# Helmet_Drop_V1_5.net
KiCad netlist of a schematic drawn in EAGLE
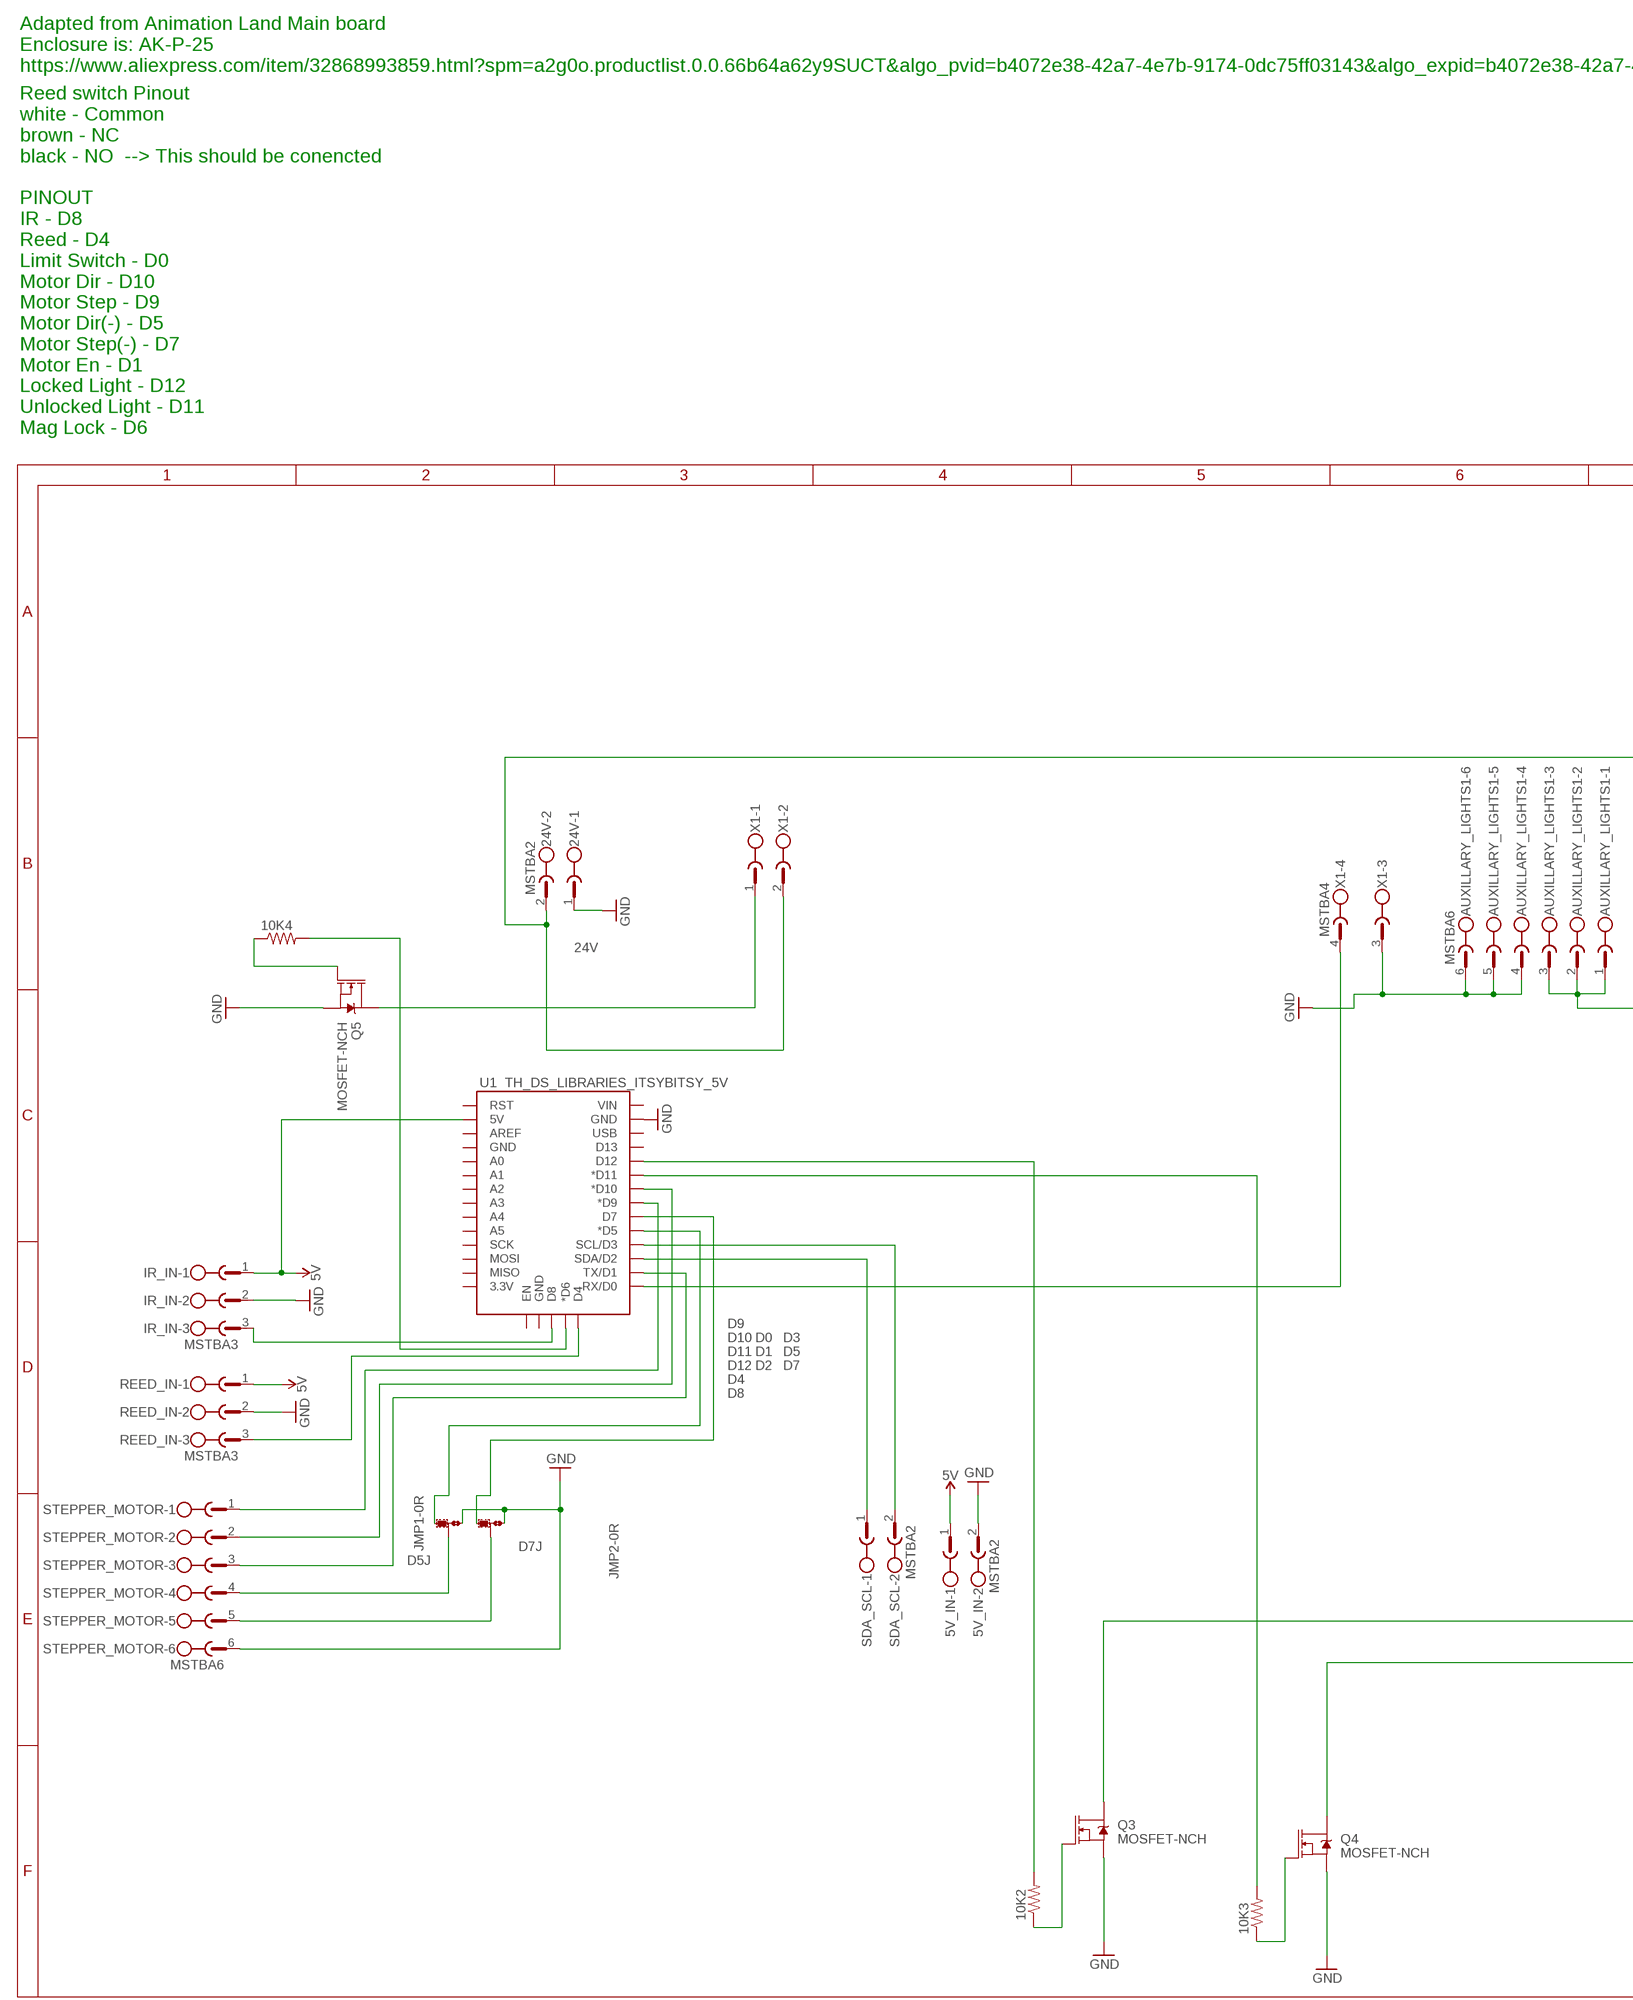
[diagram p0: schematic, sheet 1, part 1 of 2]
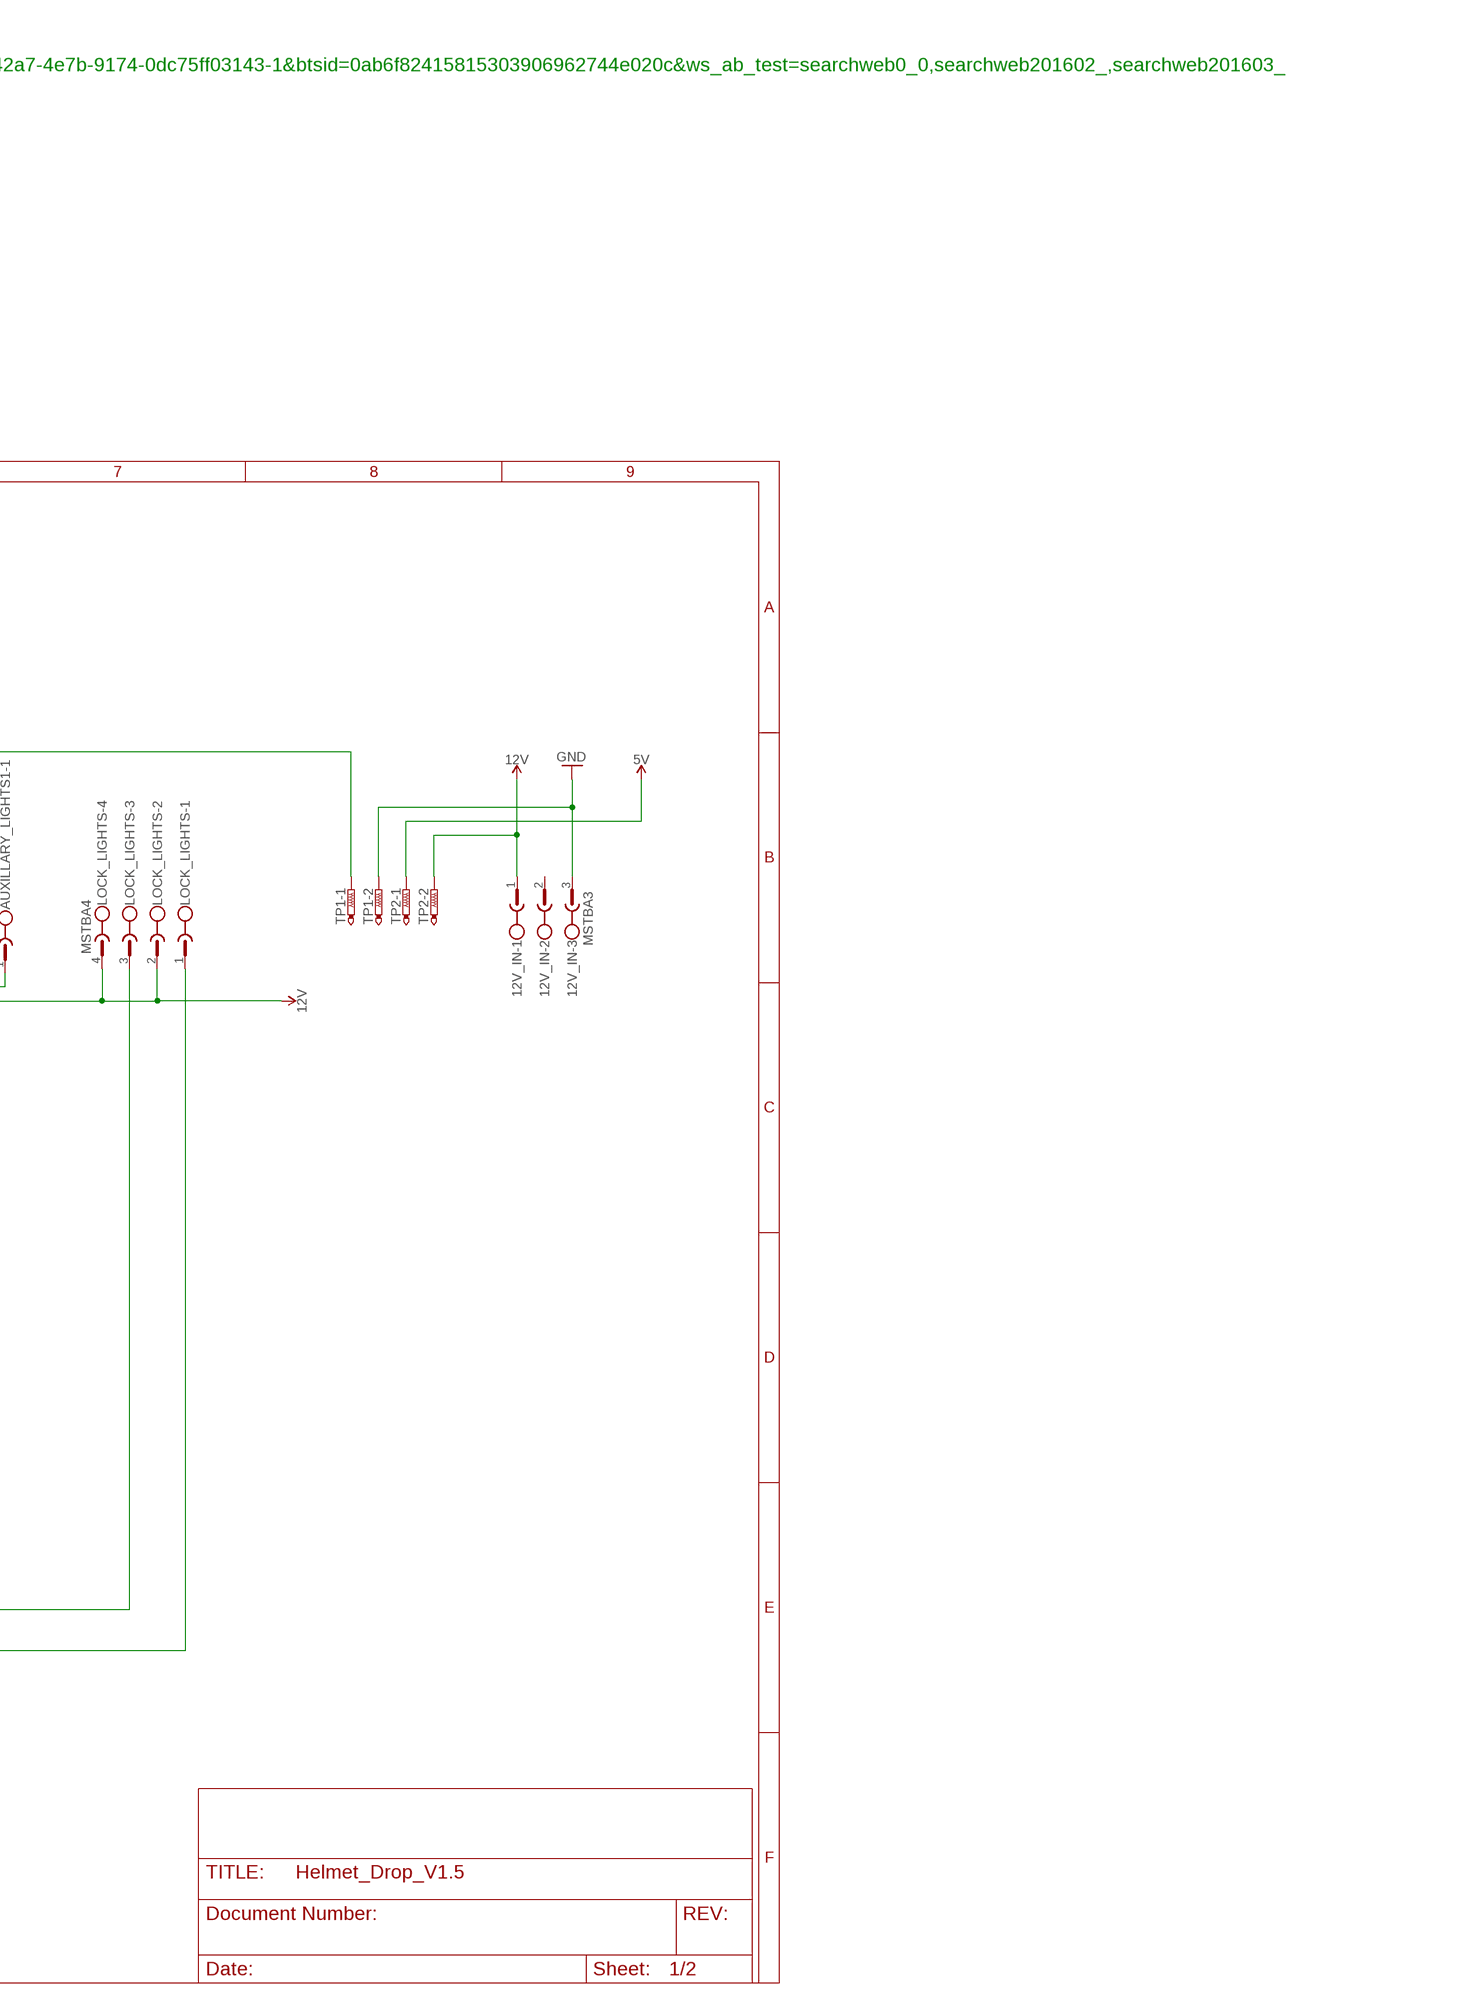
[diagram p1: schematic, sheet 1, part 2 of 2]
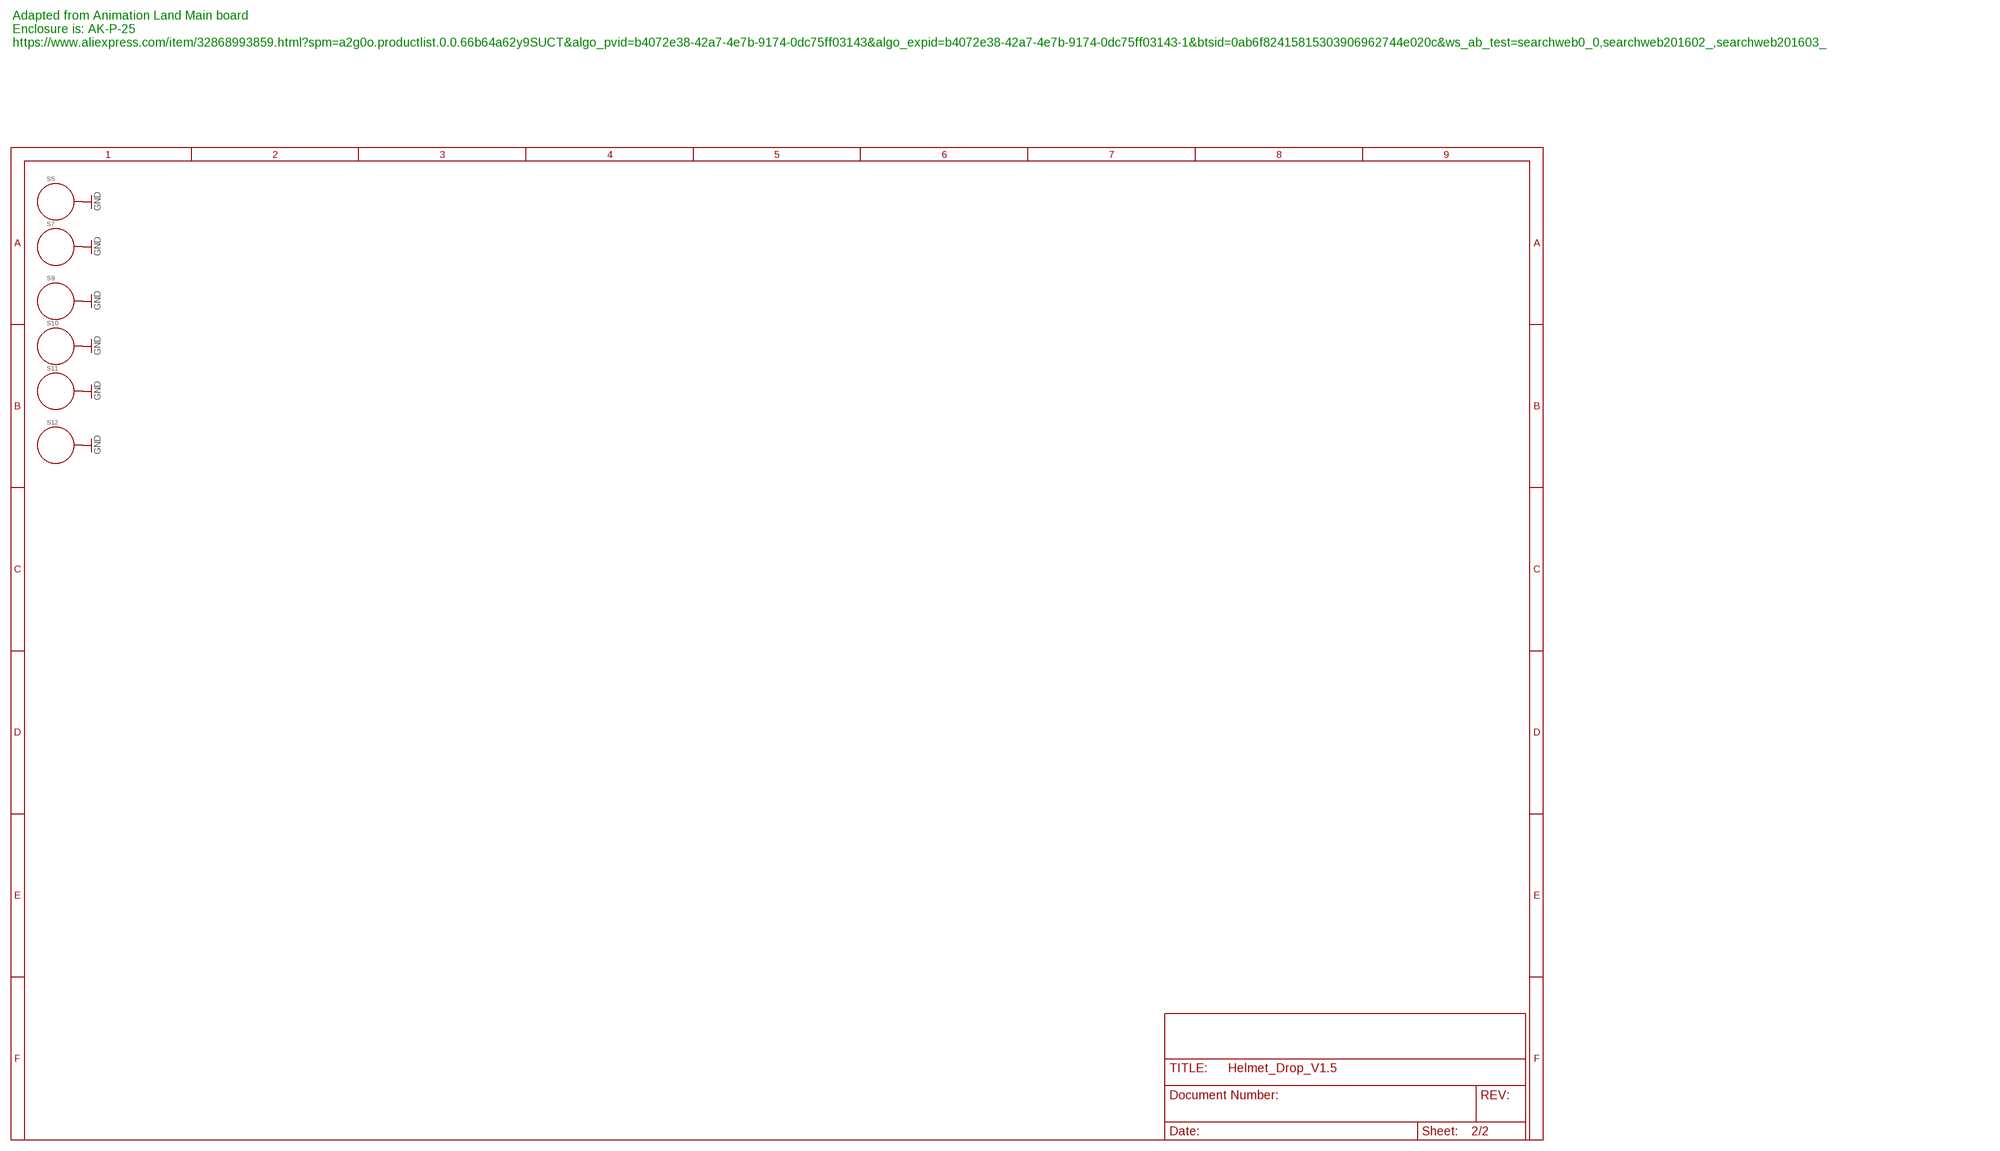
[diagram p2: schematic, sheet 2]

(export (version "E")
  (design (tool "Eeschema 10.0.6"))
  (components
    (comp (ref "S5")
      (value "STANDOFF_ELECTRICAL5-32")
      (footprint "eagle-import:STANDOFF_ELECTRICAL_5_32")
      (libsource (lib "eagle-import") (part "STANDOFF_ELECTRICAL5-32"))
    )
    (comp (ref "S7")
      (value "STANDOFF_ELECTRICAL5-32")
      (footprint "eagle-import:STANDOFF_ELECTRICAL_5_32")
      (libsource (lib "eagle-import") (part "STANDOFF_ELECTRICAL5-32"))
    )
    (comp (ref "S9")
      (value "STANDOFF_ELECTRICAL5-32")
      (footprint "eagle-import:STANDOFF_ELECTRICAL_5_32")
      (libsource (lib "eagle-import") (part "STANDOFF_ELECTRICAL5-32"))
    )
    (comp (ref "S10")
      (value "STANDOFF_ELECTRICAL5-32")
      (footprint "eagle-import:STANDOFF_ELECTRICAL_5_32")
      (libsource (lib "eagle-import") (part "STANDOFF_ELECTRICAL5-32"))
    )
    (comp (ref "S11")
      (value "STANDOFF_ELECTRICAL5-32")
      (footprint "eagle-import:STANDOFF_ELECTRICAL_5_32")
      (libsource (lib "eagle-import") (part "STANDOFF_ELECTRICAL5-32"))
    )
    (comp (ref "S12")
      (value "STANDOFF_ELECTRICAL5-32")
      (footprint "eagle-import:STANDOFF_ELECTRICAL_5_32")
      (libsource (lib "eagle-import") (part "STANDOFF_ELECTRICAL5-32"))
    )
    (comp (ref "5V_IN")
      (value "MSTBA2")
      (footprint "eagle-import:MSTBA2")
      (fields (field (name "MF") "FARNELL") (field (name "MPN") "1757242"))
      (libsource (lib "eagle-import") (part "MSTBA2"))
    )
    (comp (ref "10K2")
      (value "R-US_M0805")
      (footprint "eagle-import:M0805")
      (libsource (lib "eagle-import") (part "R-US_M0805"))
    )
    (comp (ref "10K3")
      (value "R-US_M0805")
      (footprint "eagle-import:M0805")
      (libsource (lib "eagle-import") (part "R-US_M0805"))
    )
    (comp (ref "10K4")
      (value "R-US_M0805")
      (footprint "eagle-import:M0805")
      (libsource (lib "eagle-import") (part "R-US_M0805"))
    )
    (comp (ref "12V_IN")
      (value "MSTBA3")
      (footprint "eagle-import:MSTBA3")
      (fields (field (name "MF") "FARNELL") (field (name "MPN") "1757255"))
      (libsource (lib "eagle-import") (part "MSTBA3"))
    )
    (comp (ref "24V")
      (value "MSTBA2")
      (footprint "eagle-import:MSTBA2")
      (fields (field (name "MF") "FARNELL") (field (name "MPN") "1757242"))
      (libsource (lib "eagle-import") (part "MSTBA2"))
    )
    (comp (ref "AUXILLARY_LIGHTS1")
      (value "MSTBA6")
      (footprint "eagle-import:MSTBA6")
      (fields (field (name "MF") "FARNELL") (field (name "MPN") "1757284"))
      (libsource (lib "eagle-import") (part "MSTBA6"))
    )
    (comp (ref "IR_IN")
      (value "MSTBA3")
      (footprint "eagle-import:MSTBA3")
      (fields (field (name "MF") "FARNELL") (field (name "MPN") "1757255"))
      (libsource (lib "eagle-import") (part "MSTBA3"))
    )
    (comp (ref "JMP1")
      (value "0R-JUMPB")
      (footprint "eagle-import:B0R-JMP")
      (libsource (lib "eagle-import") (part "0R-JUMPB"))
    )
    (comp (ref "JMP2")
      (value "0R-JUMPB")
      (footprint "eagle-import:B0R-JMP")
      (libsource (lib "eagle-import") (part "0R-JUMPB"))
    )
    (comp (ref "LOCK_LIGHTS")
      (value "MSTBA4")
      (footprint "eagle-import:MSTBA4")
      (fields (field (name "MF") "FARNELL") (field (name "MPN") "1757268"))
      (libsource (lib "eagle-import") (part "th_libraries_26281734_MSTBA4"))
    )
    (comp (ref "Q3")
      (value "MOSFET-NCH")
      (footprint "eagle-import:SO-8_POWER_PAK")
      (libsource (lib "eagle-import") (part "MOSFET-NCH"))
    )
    (comp (ref "Q4")
      (value "MOSFET-NCH")
      (footprint "eagle-import:SO-8_POWER_PAK")
      (libsource (lib "eagle-import") (part "MOSFET-NCH"))
    )
    (comp (ref "Q5")
      (value "MOSFET-NCH")
      (footprint "eagle-import:SO-8_POWER_PAK")
      (libsource (lib "eagle-import") (part "MOSFET-NCH"))
    )
    (comp (ref "REED_IN")
      (value "MSTBA3")
      (footprint "eagle-import:MSTBA3")
      (fields (field (name "MF") "FARNELL") (field (name "MPN") "1757255"))
      (libsource (lib "eagle-import") (part "MSTBA3"))
    )
    (comp (ref "SDA_SCL")
      (value "MSTBA2")
      (footprint "eagle-import:MSTBA2")
      (fields (field (name "MF") "FARNELL") (field (name "MPN") "1757242"))
      (libsource (lib "eagle-import") (part "MSTBA2"))
    )
    (comp (ref "STEPPER_MOTOR")
      (value "MSTBA6")
      (footprint "eagle-import:MSTBA6")
      (fields (field (name "MF") "FARNELL") (field (name "MPN") "1757284"))
      (libsource (lib "eagle-import") (part "MSTBA6"))
    )
    (comp (ref "TP1")
      (value "PTR2")
      (footprint "eagle-import:P2-38-17")
      (libsource (lib "eagle-import") (part "PTR2"))
    )
    (comp (ref "TP2")
      (value "PTR2")
      (footprint "eagle-import:P2-38-17")
      (libsource (lib "eagle-import") (part "PTR2"))
    )
    (comp (ref "U1")
      (value "TH_DS_LIBRARIES_ITSYBITSY_5V")
      (footprint "eagle-import:TH_DS_LIBRARIES_ADAFRUIT_LENOARDO")
      (libsource (lib "eagle-import") (part "TH_DS_LIBRARIES_ITSYBITSY_5V"))
    )
    (comp (ref "X1")
      (value "MSTBA4")
      (footprint "eagle-import:MSTBA4")
      (fields (field (name "MF") "FARNELL") (field (name "MPN") "1757268"))
      (libsource (lib "eagle-import") (part "MSTBA4"))
    )
  )
  (nets
    (net (code "1") (name "5V") (class "Default")
      (node (ref "5V_IN") (pin "1") (pinfunction "1_1") (pintype "passive"))
      (node (ref "IR_IN") (pin "1") (pinfunction "1_1") (pintype "passive"))
      (node (ref "REED_IN") (pin "1") (pinfunction "1_1") (pintype "passive"))
      (node (ref "TP2") (pin "TP-1") (pinfunction "TP_TP-1") (pintype "input"))
      (node (ref "U1") (pin "5V") (pinfunction "5V_5V") (pintype "bidirectional"))
    )
    (net (code "2") (name "12V") (class "Default")
      (node (ref "12V_IN") (pin "1") (pinfunction "1_1") (pintype "passive"))
      (node (ref "AUXILLARY_LIGHTS1") (pin "1") (pinfunction "1_1") (pintype "passive"))
      (node (ref "AUXILLARY_LIGHTS1") (pin "2") (pinfunction "1_2") (pintype "passive"))
      (node (ref "AUXILLARY_LIGHTS1") (pin "3") (pinfunction "1_3") (pintype "passive"))
      (node (ref "LOCK_LIGHTS") (pin "2") (pinfunction "1_2") (pintype "passive"))
      (node (ref "LOCK_LIGHTS") (pin "4") (pinfunction "1_4") (pintype "passive"))
      (node (ref "TP2") (pin "TP-2") (pinfunction "TP_TP-2") (pintype "input"))
    )
    (net (code "3") (name "24V") (class "Default")
      (node (ref "24V") (pin "2") (pinfunction "1_2") (pintype "passive"))
      (node (ref "TP1") (pin "TP-1") (pinfunction "TP_TP-1") (pintype "input"))
      (node (ref "X1") (pin "2") (pinfunction "1_2") (pintype "passive"))
    )
    (net (code "4") (name "D0") (class "Default")
      (node (ref "U1") (pin "RX") (pinfunction "RX/D0_RX") (pintype "bidirectional"))
      (node (ref "X1") (pin "4") (pinfunction "1_4") (pintype "passive"))
    )
    (net (code "5") (name "D1") (class "Default")
      (node (ref "STEPPER_MOTOR") (pin "3") (pinfunction "1_3") (pintype "passive"))
      (node (ref "U1") (pin "TX") (pinfunction "TX/D1_TX") (pintype "bidirectional"))
    )
    (net (code "6") (name "D2") (class "Default")
      (node (ref "SDA_SCL") (pin "1") (pinfunction "1_1") (pintype "passive"))
      (node (ref "U1") (pin "SDA") (pinfunction "SDA/D2_SDA") (pintype "bidirectional"))
    )
    (net (code "7") (name "D3") (class "Default")
      (node (ref "SDA_SCL") (pin "2") (pinfunction "1_2") (pintype "passive"))
      (node (ref "U1") (pin "SCL") (pinfunction "SCL/D3_SCL") (pintype "bidirectional"))
    )
    (net (code "8") (name "D4") (class "Default")
      (node (ref "REED_IN") (pin "3") (pinfunction "1_3") (pintype "passive"))
      (node (ref "U1") (pin "D4") (pinfunction "D4_D4") (pintype "bidirectional"))
    )
    (net (code "9") (name "D5") (class "Default")
      (node (ref "JMP1") (pin "3") (pinfunction "3_3") (pintype "passive"))
      (node (ref "U1") (pin "D5") (pinfunction "*D5_D5") (pintype "bidirectional"))
    )
    (net (code "10") (name "D5J") (class "Default")
      (node (ref "JMP1") (pin "2") (pinfunction "2_2") (pintype "passive"))
      (node (ref "STEPPER_MOTOR") (pin "4") (pinfunction "1_4") (pintype "passive"))
    )
    (net (code "11") (name "D7") (class "Default")
      (node (ref "JMP2") (pin "3") (pinfunction "3_3") (pintype "passive"))
      (node (ref "U1") (pin "D7") (pinfunction "D7_D7") (pintype "bidirectional"))
    )
    (net (code "12") (name "D7J") (class "Default")
      (node (ref "JMP2") (pin "2") (pinfunction "2_2") (pintype "passive"))
      (node (ref "STEPPER_MOTOR") (pin "5") (pinfunction "1_5") (pintype "passive"))
    )
    (net (code "13") (name "D8") (class "Default")
      (node (ref "IR_IN") (pin "3") (pinfunction "1_3") (pintype "passive"))
      (node (ref "U1") (pin "D8") (pinfunction "D8_D8") (pintype "bidirectional"))
    )
    (net (code "14") (name "D9") (class "Default")
      (node (ref "STEPPER_MOTOR") (pin "1") (pinfunction "1_1") (pintype "passive"))
      (node (ref "U1") (pin "D9") (pinfunction "*D9_D9") (pintype "bidirectional"))
    )
    (net (code "15") (name "D10") (class "Default")
      (node (ref "STEPPER_MOTOR") (pin "2") (pinfunction "1_2") (pintype "passive"))
      (node (ref "U1") (pin "D10") (pinfunction "*D10_D10") (pintype "bidirectional"))
    )
    (net (code "16") (name "D11") (class "Default")
      (node (ref "10K3") (pin "2") (pinfunction "2_2") (pintype "passive"))
      (node (ref "U1") (pin "D11") (pinfunction "*D11_D11") (pintype "bidirectional"))
    )
    (net (code "17") (name "D12") (class "Default")
      (node (ref "10K2") (pin "2") (pinfunction "2_2") (pintype "passive"))
      (node (ref "U1") (pin "D12") (pinfunction "D12_D12") (pintype "bidirectional"))
    )
    (net (code "18") (name "GND") (class "Default")
      (node (ref "12V_IN") (pin "3") (pinfunction "1_3") (pintype "passive"))
      (node (ref "24V") (pin "1") (pinfunction "1_1") (pintype "passive"))
      (node (ref "5V_IN") (pin "2") (pinfunction "1_2") (pintype "passive"))
      (node (ref "AUXILLARY_LIGHTS1") (pin "4") (pinfunction "1_4") (pintype "passive"))
      (node (ref "AUXILLARY_LIGHTS1") (pin "5") (pinfunction "1_5") (pintype "passive"))
      (node (ref "AUXILLARY_LIGHTS1") (pin "6") (pinfunction "1_6") (pintype "passive"))
      (node (ref "IR_IN") (pin "2") (pinfunction "1_2") (pintype "passive"))
      (node (ref "JMP1") (pin "1") (pinfunction "1_1") (pintype "passive"))
      (node (ref "JMP2") (pin "1") (pinfunction "1_1") (pintype "passive"))
      (node (ref "Q3") (pin "S") (pinfunction "S_S") (pintype "bidirectional"))
      (node (ref "Q4") (pin "S") (pinfunction "S_S") (pintype "bidirectional"))
      (node (ref "Q5") (pin "S") (pinfunction "S_S") (pintype "bidirectional"))
      (node (ref "REED_IN") (pin "2") (pinfunction "1_2") (pintype "passive"))
      (node (ref "S10") (pin "P1") (pinfunction "P$1_P1") (pintype "bidirectional"))
      (node (ref "S11") (pin "P1") (pinfunction "P$1_P1") (pintype "bidirectional"))
      (node (ref "S12") (pin "P1") (pinfunction "P$1_P1") (pintype "bidirectional"))
      (node (ref "S5") (pin "P1") (pinfunction "P$1_P1") (pintype "bidirectional"))
      (node (ref "S7") (pin "P1") (pinfunction "P$1_P1") (pintype "bidirectional"))
      (node (ref "S9") (pin "P1") (pinfunction "P$1_P1") (pintype "bidirectional"))
      (node (ref "STEPPER_MOTOR") (pin "6") (pinfunction "1_6") (pintype "passive"))
      (node (ref "TP1") (pin "TP-2") (pinfunction "TP_TP-2") (pintype "input"))
      (node (ref "U1") (pin "GND@2") (pinfunction "GND_GND@2") (pintype "bidirectional"))
      (node (ref "X1") (pin "3") (pinfunction "1_3") (pintype "passive"))
    )
    (net (code "19") (name "Net-(10K2-Pad1)") (class "Default")
      (node (ref "10K2") (pin "1") (pinfunction "1_1") (pintype "passive"))
      (node (ref "Q3") (pin "G") (pinfunction "G_G") (pintype "bidirectional"))
    )
    (net (code "20") (name "Net-(10K3-Pad1)") (class "Default")
      (node (ref "10K3") (pin "1") (pinfunction "1_1") (pintype "passive"))
      (node (ref "Q4") (pin "G") (pinfunction "G_G") (pintype "bidirectional"))
    )
    (net (code "21") (name "Net-(10K4-Pad1)") (class "Default")
      (node (ref "10K4") (pin "1") (pinfunction "1_1") (pintype "passive"))
      (node (ref "Q5") (pin "G") (pinfunction "G_G") (pintype "bidirectional"))
    )
    (net (code "22") (name "Net-(LOCK_LIGHTSC-1)") (class "Default")
      (node (ref "LOCK_LIGHTS") (pin "3") (pinfunction "1_3") (pintype "passive"))
      (node (ref "Q3") (pin "D1") (pinfunction "D_D1") (pintype "bidirectional"))
    )
    (net (code "23") (name "Net-(Q4-D)") (class "Default")
      (node (ref "LOCK_LIGHTS") (pin "1") (pinfunction "1_1") (pintype "passive"))
      (node (ref "Q4") (pin "D1") (pinfunction "D_D1") (pintype "bidirectional"))
    )
    (net (code "24") (name "Net-(Q5-D)") (class "Default")
      (node (ref "Q5") (pin "D1") (pinfunction "D_D1") (pintype "bidirectional"))
      (node (ref "X1") (pin "1") (pinfunction "1_1") (pintype "passive"))
    )
    (net (code "25") (name "Net-(U1-*D6)") (class "Default")
      (node (ref "10K4") (pin "2") (pinfunction "2_2") (pintype "passive"))
      (node (ref "U1") (pin "D6") (pinfunction "*D6_D6") (pintype "bidirectional"))
    )
    (net (code "26") (name "unconnected-(12V_INB-1-Pad2)") (class "Default")
      (node (ref "12V_IN") (pin "2") (pinfunction "1_2") (pintype "passive"))
    )
    (net (code "27") (name "unconnected-(U1-3.3V-Pad3V)") (class "Default")
      (node (ref "U1") (pin "3V") (pinfunction "3.3V_3V") (pintype "bidirectional"))
    )
    (net (code "28") (name "unconnected-(U1-GND-PadGND@0)") (class "Default")
      (node (ref "U1") (pin "GND@0") (pinfunction "GND_GND@0") (pintype "bidirectional"))
    )
    (net (code "29") (name "unconnected-(U1-GND-PadGND@1)") (class "Default")
      (node (ref "U1") (pin "GND@1") (pinfunction "GND_GND@1") (pintype "bidirectional"))
    )
    (net (code "30") (name "unconnected-(U1-PadA0)") (class "Default")
      (node (ref "U1") (pin "A0") (pinfunction "A0_A0") (pintype "bidirectional"))
    )
    (net (code "31") (name "unconnected-(U1-PadA1)") (class "Default")
      (node (ref "U1") (pin "A1") (pinfunction "A1_A1") (pintype "bidirectional"))
    )
    (net (code "32") (name "unconnected-(U1-PadA2)") (class "Default")
      (node (ref "U1") (pin "A2") (pinfunction "A2_A2") (pintype "bidirectional"))
    )
    (net (code "33") (name "unconnected-(U1-PadA3)") (class "Default")
      (node (ref "U1") (pin "A3") (pinfunction "A3_A3") (pintype "bidirectional"))
    )
    (net (code "34") (name "unconnected-(U1-PadA4)") (class "Default")
      (node (ref "U1") (pin "A4") (pinfunction "A4_A4") (pintype "bidirectional"))
    )
    (net (code "35") (name "unconnected-(U1-PadA5)") (class "Default")
      (node (ref "U1") (pin "A5") (pinfunction "A5_A5") (pintype "bidirectional"))
    )
    (net (code "36") (name "unconnected-(U1-PadAREF)") (class "Default")
      (node (ref "U1") (pin "AREF") (pinfunction "AREF_AREF") (pintype "bidirectional"))
    )
    (net (code "37") (name "unconnected-(U1-PadD13)") (class "Default")
      (node (ref "U1") (pin "D13") (pinfunction "D13_D13") (pintype "bidirectional"))
    )
    (net (code "38") (name "unconnected-(U1-PadEN)") (class "Default")
      (node (ref "U1") (pin "EN") (pinfunction "EN_EN") (pintype "bidirectional"))
    )
    (net (code "39") (name "unconnected-(U1-PadMISO)") (class "Default")
      (node (ref "U1") (pin "MISO") (pinfunction "MISO_MISO") (pintype "bidirectional"))
    )
    (net (code "40") (name "unconnected-(U1-PadMOSI)") (class "Default")
      (node (ref "U1") (pin "MOSI") (pinfunction "MOSI_MOSI") (pintype "bidirectional"))
    )
    (net (code "41") (name "unconnected-(U1-PadSCK)") (class "Default")
      (node (ref "U1") (pin "SCK") (pinfunction "SCK_SCK") (pintype "bidirectional"))
    )
    (net (code "42") (name "unconnected-(U1-PadUSB)") (class "Default")
      (node (ref "U1") (pin "USB") (pinfunction "USB_USB") (pintype "bidirectional"))
    )
    (net (code "43") (name "unconnected-(U1-PadVIN)") (class "Default")
      (node (ref "U1") (pin "VIN") (pinfunction "VIN_VIN") (pintype "bidirectional"))
    )
    (net (code "44") (name "unconnected-(U1-RST-PadRES)") (class "Default")
      (node (ref "U1") (pin "RES") (pinfunction "RST_RES") (pintype "bidirectional"))
    )
  )
)
